# FTDI.net
KiCad netlist of a schematic drawn in Altium Designer
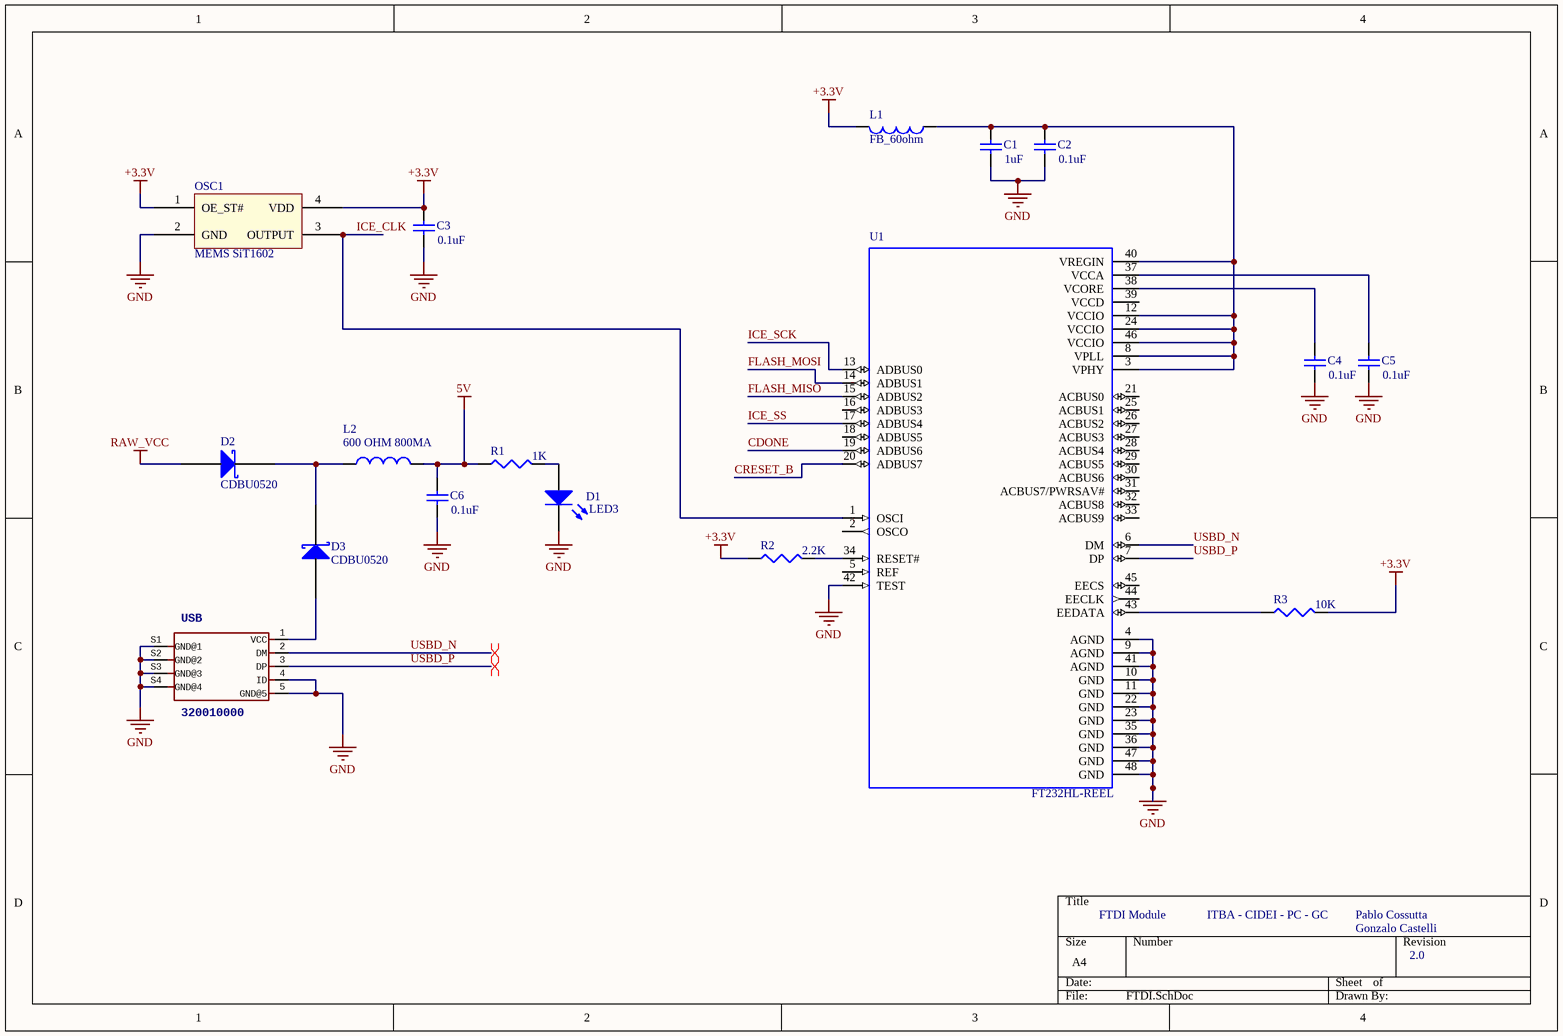
[diagram p0: FTDI.SchDoc]

(export (version "E")
  (design (tool "Eeschema 10.0.6"))
  (components
    (comp (ref "C1")
      (value "1uF")
      (footprint "C0402")
      (description "Capacitor (Semiconductor SIM Model)")
      (fields
        (field (name "MANUFACTURER") "TDK Corporation")
        (field (name "MANUFACTURER PART NUMBER") "CGB2A1JB1E105M033BC")
        (field (name "PUBLISHER") "Altium Limited")
      )
      (libsource (lib "Miscellaneous Devices") (part "Cap Semi"))
    )
    (comp (ref "C2")
      (value "0.1uF")
      (footprint "C0402")
      (description "Capacitor (Semiconductor SIM Model)")
      (fields
        (field (name "MANUFACTURER") "Samsung Electro-Mechanics")
        (field (name "MANUFACTURER PART NUMBER") "CL05B104KA5NNNC")
        (field (name "PUBLISHER") "Altium Limited")
      )
      (libsource (lib "Miscellaneous Devices") (part "Cap Semi"))
    )
    (comp (ref "C3")
      (value "0.1uF")
      (footprint "C0402")
      (description "Capacitor (Semiconductor SIM Model)")
      (fields
        (field (name "MANUFACTURER") "Samsung Electro-Mechanics")
        (field (name "MANUFACTURER PART NUMBER") "CL05B104KA5NNNC")
        (field (name "PUBLISHER") "Altium Limited")
      )
      (libsource (lib "Miscellaneous Devices") (part "Cap Semi"))
    )
    (comp (ref "C4")
      (value "0.1uF")
      (footprint "C0402")
      (description "Capacitor (Semiconductor SIM Model)")
      (fields
        (field (name "MANUFACTURER") "Samsung Electro-Mechanics")
        (field (name "MANUFACTURER PART NUMBER") "CL05B104KA5NNNC")
        (field (name "PUBLISHER") "Altium Limited")
      )
      (libsource (lib "Miscellaneous Devices") (part "Cap Semi"))
    )
    (comp (ref "C5")
      (value "0.1uF")
      (footprint "C0402")
      (description "Capacitor (Semiconductor SIM Model)")
      (fields
        (field (name "MANUFACTURER") "Samsung Electro-Mechanics")
        (field (name "MANUFACTURER PART NUMBER") "CL05B104KA5NNNC")
        (field (name "PUBLISHER") "Altium Limited")
      )
      (libsource (lib "Miscellaneous Devices") (part "Cap Semi"))
    )
    (comp (ref "C6")
      (value "0.1uF")
      (footprint "C0402")
      (description "Capacitor (Semiconductor SIM Model)")
      (fields
        (field (name "MANUFACTURER") "Samsung Electro-Mechanics")
        (field (name "MANUFACTURER PART NUMBER") "CL05B104KA5NNNC")
        (field (name "PUBLISHER") "Altium Limited")
      )
      (libsource (lib "Miscellaneous Devices") (part "Cap Semi"))
    )
    (comp (ref "D1")
      (value "LED3")
      (footprint "LED-0603")
      (description "Typical BLUE SiC LED")
      (fields
        (field (name "MANUFACTURER") "Lite-On Inc.")
        (field (name "MANUFACTURER PART NUMBER") "LTST-C190TBKT")
        (field (name "PUBLISHER") "Altium Limited")
      )
      (libsource (lib "Miscellaneous Devices") (part "LED3"))
    )
    (comp (ref "D2")
      (value "CDBU0520")
      (footprint "CDBU0520")
      (description "DIODE SCHOTTKY 20V 500MA 0603")
      (fields (field (name "MANUFACTURER") "Comchip Technology"))
      (libsource (lib "FPGAlib") (part "CDBU0520"))
    )
    (comp (ref "D3")
      (value "CDBU0520")
      (footprint "CDBU0520")
      (description "DIODE SCHOTTKY 20V 500MA 0603")
      (fields (field (name "MANUFACTURER") "Comchip Technology"))
      (libsource (lib "FPGAlib") (part "CDBU0520"))
    )
    (comp (ref "L1")
      (value "FB_60ohm")
      (footprint "J1-0603")
      (description "Inductor")
      (fields
        (field (name "MANUFACTURER") "Laird-Signal Integrity Products")
        (field (name "MANUFACTURER PART NUMBER") "HI0603P600R-10")
        (field (name "PUBLISHER") "Altium Limited")
      )
      (libsource (lib "Miscellaneous Devices") (part "Inductor"))
    )
    (comp (ref "L2")
      (value "600 OHM 800MA")
      (footprint "J1-0603")
      (description "Inductor")
      (fields
        (field (name "MANUFACTURER") "Murata Electronics North America")
        (field (name "MANUFACTURER PART NUMBER") "BLM18HE601SN1D")
        (field (name "PUBLISHER") "Altium Limited")
      )
      (libsource (lib "Miscellaneous Devices") (part "Inductor"))
    )
    (comp (ref "OSC1")
      (value "MEMS SiT1602")
      (footprint "oscMEMS1602")
      (description "MEMS OSC XO 12.0000MHZ LVCMOS")
      (fields
        (field (name "MANUFACTURER") "SiTIME")
        (field (name "MANUFACTURER PART NUMBER") "SIT1602AC-13-33E-12.000000G")
      )
      (libsource (lib "FPGAlib") (part "SIT1602AC-13-33E-12.000000G"))
    )
    (comp (ref "R1")
      (value "1K")
      (footprint "R0402")
      (description "Resistor")
      (fields
        (field (name "MANUFACTURER") "Yageo")
        (field (name "MANUFACTURER PART NUMBER") "RC0402JR-071KL")
        (field (name "PUBLISHER") "Altium Limited")
      )
      (libsource (lib "Miscellaneous Devices") (part "Res3"))
    )
    (comp (ref "R2")
      (value "2.2K")
      (footprint "R0402")
      (description "Resistor")
      (fields
        (field (name "MANUFACTURER") "Yageo")
        (field (name "MANUFACTURER PART NUMBER") "RC0402FR-072K2L")
        (field (name "PUBLISHER") "Altium Limited")
      )
      (libsource (lib "Miscellaneous Devices") (part "Res3"))
    )
    (comp (ref "R3")
      (value "10K")
      (footprint "Seeed-Resistor:R0402")
      (description "Resistor")
      (fields
        (field (name "MANUFACTURER") "Yageo")
        (field (name "MANUFACTURER PART NUMBER") "RC0402JR-0710KP")
        (field (name "PUBLISHER") "Altium Limited")
      )
      (libsource (lib "Miscellaneous Devices") (part "Res3"))
    )
    (comp (ref "U1")
      (value "FT232HL-REEL")
      (footprint "QFP50P900X900X160-48N")
      (description "IC HS USB TO UART/FIFO 48LQFP")
      (fields (field (name "MANUFACTURER") "FTDI, Future Technology Devices International Ltd"))
      (libsource (lib "FPGAlib") (part "FT232HL-REEL"))
    )
    (comp (ref "USB")
      (value "320010000")
      (footprint "MICRO-USB5+4P-SMD-0.65-B")
      (description "CONN USB MICRO B RECPT SMT R/A")
      (fields
        (field (name "MANUFACTURER") "Amphenol FCI")
        (field (name "MANUFACTURER PART NUMBER") "10118193-0001LF")
      )
      (libsource (lib "FPGAlib") (part "USB MICRO B"))
    )
  )
  (nets
    (net (code "1") (name "+3.3V") (class "Default")
      (node (ref "C3") (pin "2") (pinfunction "2_2") (pintype "passive"))
      (node (ref "L1") (pin "2") (pinfunction "2_2") (pintype "passive"))
      (node (ref "OSC1") (pin "1") (pinfunction "OE_ST#_1") (pintype "passive"))
      (node (ref "OSC1") (pin "4") (pinfunction "VDD_4") (pintype "passive"))
      (node (ref "R2") (pin "1") (pinfunction "1_1") (pintype "passive"))
      (node (ref "R3") (pin "2") (pinfunction "2_2") (pintype "passive"))
    )
    (net (code "2") (name "/CDONE") (class "Default")
      (node (ref "U1") (pin "19") (pinfunction "ADBUS6_19") (pintype "bidirectional"))
    )
    (net (code "3") (name "/CRESET_B") (class "Default")
      (node (ref "U1") (pin "20") (pinfunction "ADBUS7_20") (pintype "bidirectional"))
    )
    (net (code "4") (name "/FLASH_MISO") (class "Default")
      (node (ref "U1") (pin "15") (pinfunction "ADBUS2_15") (pintype "bidirectional"))
    )
    (net (code "5") (name "/FLASH_MOSI") (class "Default")
      (node (ref "U1") (pin "14") (pinfunction "ADBUS1_14") (pintype "bidirectional"))
    )
    (net (code "6") (name "/ICE_CLK") (class "Default")
      (node (ref "OSC1") (pin "3") (pinfunction "OUTPUT_3") (pintype "passive"))
      (node (ref "U1") (pin "1") (pinfunction "OSCI_1") (pintype "input"))
    )
    (net (code "7") (name "/ICE_SCK") (class "Default")
      (node (ref "U1") (pin "13") (pinfunction "ADBUS0_13") (pintype "bidirectional"))
    )
    (net (code "8") (name "/ICE_SS") (class "Default")
      (node (ref "U1") (pin "17") (pinfunction "ADBUS4_17") (pintype "bidirectional"))
    )
    (net (code "9") (name "/USBD_N") (class "Default")
      (node (ref "U1") (pin "6") (pinfunction "DM_6") (pintype "bidirectional"))
      (node (ref "USB") (pin "2") (pinfunction "DM_2") (pintype "passive"))
    )
    (net (code "10") (name "/USBD_P") (class "Default")
      (node (ref "U1") (pin "7") (pinfunction "DP_7") (pintype "bidirectional"))
      (node (ref "USB") (pin "3") (pinfunction "DP_3") (pintype "passive"))
    )
    (net (code "11") (name "5V") (class "Default")
      (node (ref "C6") (pin "2") (pinfunction "2_2") (pintype "passive"))
      (node (ref "L2") (pin "2") (pinfunction "2_2") (pintype "passive"))
      (node (ref "R1") (pin "1") (pinfunction "1_1") (pintype "passive"))
    )
    (net (code "12") (name "GND") (class "Default")
      (node (ref "C1") (pin "1") (pinfunction "1_1") (pintype "passive"))
      (node (ref "C2") (pin "1") (pinfunction "1_1") (pintype "passive"))
      (node (ref "C3") (pin "1") (pinfunction "1_1") (pintype "passive"))
      (node (ref "C4") (pin "1") (pinfunction "1_1") (pintype "passive"))
      (node (ref "C5") (pin "1") (pinfunction "1_1") (pintype "passive"))
      (node (ref "C6") (pin "1") (pinfunction "1_1") (pintype "passive"))
      (node (ref "D1") (pin "2") (pinfunction "K_2") (pintype "passive"))
      (node (ref "OSC1") (pin "2") (pinfunction "GND_2") (pintype "passive"))
      (node (ref "U1") (pin "10") (pinfunction "GND_10") (pintype "power_in"))
      (node (ref "U1") (pin "11") (pinfunction "GND_11") (pintype "power_in"))
      (node (ref "U1") (pin "22") (pinfunction "GND_22") (pintype "power_in"))
      (node (ref "U1") (pin "23") (pinfunction "GND_23") (pintype "power_in"))
      (node (ref "U1") (pin "35") (pinfunction "GND_35") (pintype "power_in"))
      (node (ref "U1") (pin "36") (pinfunction "GND_36") (pintype "power_in"))
      (node (ref "U1") (pin "4") (pinfunction "AGND_4") (pintype "power_in"))
      (node (ref "U1") (pin "41") (pinfunction "AGND_41") (pintype "power_in"))
      (node (ref "U1") (pin "42") (pinfunction "TEST_42") (pintype "input"))
      (node (ref "U1") (pin "47") (pinfunction "GND_47") (pintype "power_in"))
      (node (ref "U1") (pin "48") (pinfunction "GND_48") (pintype "power_in"))
      (node (ref "U1") (pin "9") (pinfunction "AGND_9") (pintype "power_in"))
      (node (ref "USB") (pin "4") (pinfunction "ID_4") (pintype "passive"))
      (node (ref "USB") (pin "5") (pinfunction "GND@5_5") (pintype "passive"))
      (node (ref "USB") (pin "S1") (pinfunction "GND@1_S1") (pintype "passive"))
      (node (ref "USB") (pin "S2") (pinfunction "GND@2_S2") (pintype "passive"))
      (node (ref "USB") (pin "S3") (pinfunction "GND@3_S3") (pintype "passive"))
      (node (ref "USB") (pin "S4") (pinfunction "GND@4_S4") (pintype "passive"))
    )
    (net (code "13") (name "Net-(D1-A)") (class "Default")
      (node (ref "D1") (pin "1") (pinfunction "A_1") (pintype "passive"))
      (node (ref "R1") (pin "2") (pinfunction "2_2") (pintype "passive"))
    )
    (net (code "14") (name "Net-(D2-Pad2)") (class "Default")
      (node (ref "D2") (pin "2") (pintype "passive"))
      (node (ref "D3") (pin "2") (pintype "passive"))
      (node (ref "L2") (pin "1") (pinfunction "1_1") (pintype "passive"))
    )
    (net (code "15") (name "Net-(U1-EEDATA)") (class "Default")
      (node (ref "R3") (pin "1") (pinfunction "1_1") (pintype "passive"))
      (node (ref "U1") (pin "43") (pinfunction "EEDATA_43") (pintype "bidirectional"))
    )
    (net (code "16") (name "Net-(U1-RESET#)") (class "Default")
      (node (ref "R2") (pin "2") (pinfunction "2_2") (pintype "passive"))
      (node (ref "U1") (pin "34") (pinfunction "RESET#_34") (pintype "input"))
    )
    (net (code "17") (name "Net-(U1-VCCA)") (class "Default")
      (node (ref "C5") (pin "2") (pinfunction "2_2") (pintype "passive"))
      (node (ref "U1") (pin "37") (pinfunction "VCCA_37") (pintype "power_in"))
    )
    (net (code "18") (name "Net-(U1-VCORE)") (class "Default")
      (node (ref "C4") (pin "2") (pinfunction "2_2") (pintype "passive"))
      (node (ref "U1") (pin "38") (pinfunction "VCORE_38") (pintype "power_in"))
    )
    (net (code "19") (name "Net-(U1-VPHY)") (class "Default")
      (node (ref "C1") (pin "2") (pinfunction "2_2") (pintype "passive"))
      (node (ref "C2") (pin "2") (pinfunction "2_2") (pintype "passive"))
      (node (ref "L1") (pin "1") (pinfunction "1_1") (pintype "passive"))
      (node (ref "U1") (pin "12") (pinfunction "VCCIO_12") (pintype "power_in"))
      (node (ref "U1") (pin "24") (pinfunction "VCCIO_24") (pintype "power_in"))
      (node (ref "U1") (pin "3") (pinfunction "VPHY_3") (pintype "power_in"))
      (node (ref "U1") (pin "40") (pinfunction "VREGIN_40") (pintype "power_in"))
      (node (ref "U1") (pin "46") (pinfunction "VCCIO_46") (pintype "power_in"))
      (node (ref "U1") (pin "8") (pinfunction "VPLL_8") (pintype "power_in"))
    )
    (net (code "20") (name "Net-(USB-VCC)") (class "Default")
      (node (ref "D3") (pin "1") (pintype "passive"))
      (node (ref "USB") (pin "1") (pinfunction "VCC_1") (pintype "passive"))
    )
    (net (code "21") (name "RAW_VCC") (class "Default") (node (ref "D2") (pin "1") (pintype "passive")))
    (net (code "22") (name "unconnected-(U1-ACBUS0-Pad21)") (class "Default")
      (node (ref "U1") (pin "21") (pinfunction "ACBUS0_21") (pintype "bidirectional"))
    )
    (net (code "23") (name "unconnected-(U1-ACBUS1-Pad25)") (class "Default")
      (node (ref "U1") (pin "25") (pinfunction "ACBUS1_25") (pintype "bidirectional"))
    )
    (net (code "24") (name "unconnected-(U1-ACBUS2-Pad26)") (class "Default")
      (node (ref "U1") (pin "26") (pinfunction "ACBUS2_26") (pintype "bidirectional"))
    )
    (net (code "25") (name "unconnected-(U1-ACBUS3-Pad27)") (class "Default")
      (node (ref "U1") (pin "27") (pinfunction "ACBUS3_27") (pintype "bidirectional"))
    )
    (net (code "26") (name "unconnected-(U1-ACBUS4-Pad28)") (class "Default")
      (node (ref "U1") (pin "28") (pinfunction "ACBUS4_28") (pintype "bidirectional"))
    )
    (net (code "27") (name "unconnected-(U1-ACBUS5-Pad29)") (class "Default")
      (node (ref "U1") (pin "29") (pinfunction "ACBUS5_29") (pintype "bidirectional"))
    )
    (net (code "28") (name "unconnected-(U1-ACBUS6-Pad30)") (class "Default")
      (node (ref "U1") (pin "30") (pinfunction "ACBUS6_30") (pintype "bidirectional"))
    )
    (net (code "29") (name "unconnected-(U1-ACBUS7{slash}PWRSAV#-Pad31)") (class "Default")
      (node (ref "U1") (pin "31") (pinfunction "ACBUS7/PWRSAV#_31") (pintype "bidirectional"))
    )
    (net (code "30") (name "unconnected-(U1-ACBUS8-Pad32)") (class "Default")
      (node (ref "U1") (pin "32") (pinfunction "ACBUS8_32") (pintype "bidirectional"))
    )
    (net (code "31") (name "unconnected-(U1-ACBUS9-Pad33)") (class "Default")
      (node (ref "U1") (pin "33") (pinfunction "ACBUS9_33") (pintype "bidirectional"))
    )
    (net (code "32") (name "unconnected-(U1-ADBUS3-Pad16)") (class "Default")
      (node (ref "U1") (pin "16") (pinfunction "ADBUS3_16") (pintype "bidirectional"))
    )
    (net (code "33") (name "unconnected-(U1-ADBUS5-Pad18)") (class "Default")
      (node (ref "U1") (pin "18") (pinfunction "ADBUS5_18") (pintype "bidirectional"))
    )
    (net (code "34") (name "unconnected-(U1-EECLK-Pad44)") (class "Default")
      (node (ref "U1") (pin "44") (pinfunction "EECLK_44") (pintype "output"))
    )
    (net (code "35") (name "unconnected-(U1-EECS-Pad45)") (class "Default")
      (node (ref "U1") (pin "45") (pinfunction "EECS_45") (pintype "bidirectional"))
    )
    (net (code "36") (name "unconnected-(U1-OSCO-Pad2)") (class "Default")
      (node (ref "U1") (pin "2") (pinfunction "OSCO_2") (pintype "output"))
    )
    (net (code "37") (name "unconnected-(U1-REF-Pad5)") (class "Default")
      (node (ref "U1") (pin "5") (pinfunction "REF_5") (pintype "input"))
    )
    (net (code "38") (name "unconnected-(U1-VCCD-Pad39)") (class "Default")
      (node (ref "U1") (pin "39") (pinfunction "VCCD_39") (pintype "power_in"))
    )
  )
)
